# watch_1_2.net
KiCad netlist of a schematic drawn in EAGLE
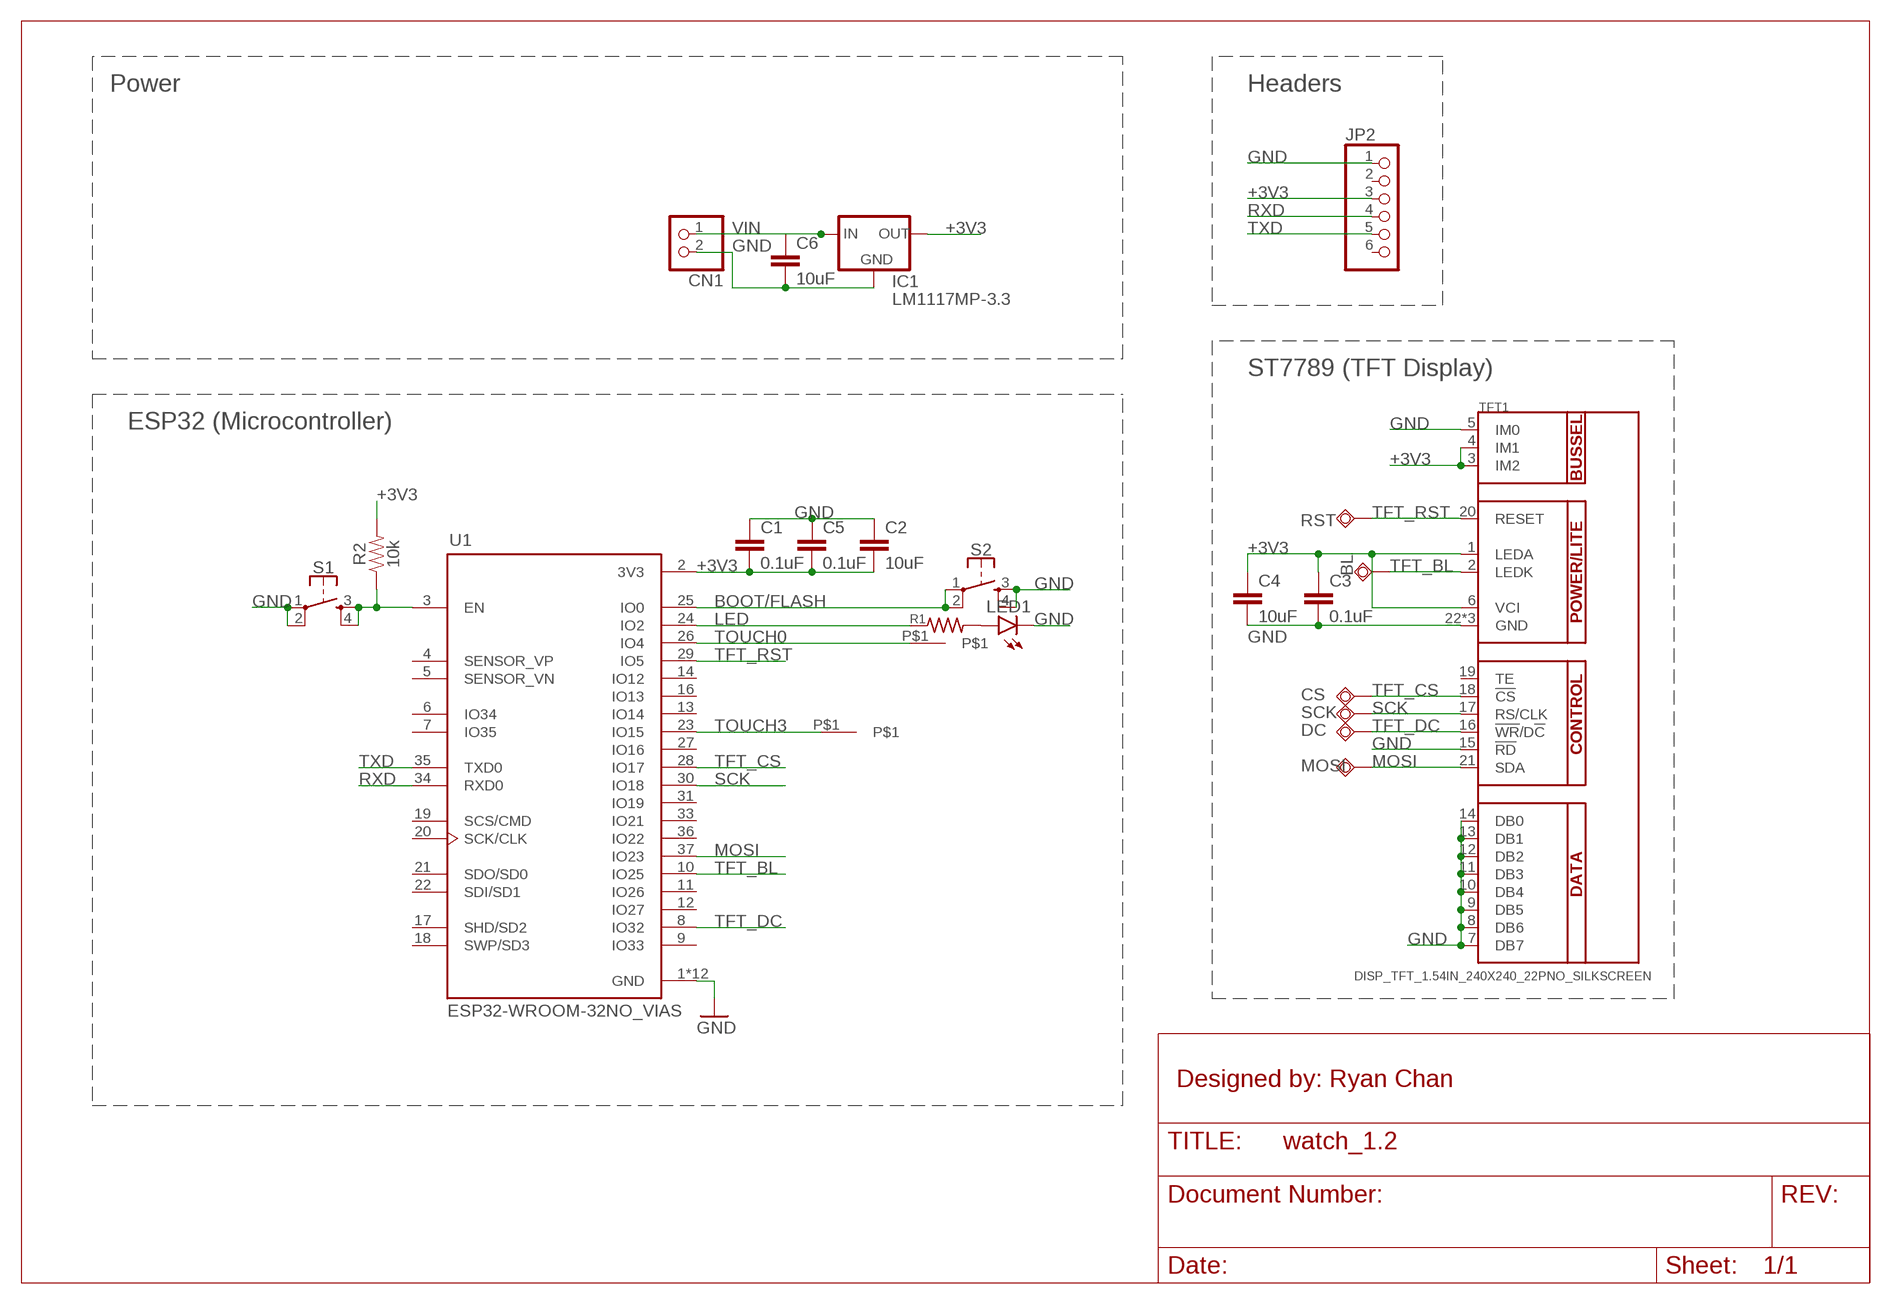
[diagram p0: schematic, sheet 1]

(export (version "E")
  (design (tool "Eeschema 10.0.6"))
  (components
    (comp (ref "BL")
      (value "TPSQTP20R")
      (footprint "eagle-import:TP20R")
      (libsource (lib "eagle-import") (part "TPSQTP20R"))
    )
    (comp (ref "C1")
      (value "0.1uF")
      (footprint "eagle-import:C0603")
      (libsource (lib "eagle-import") (part "C-EUC0603"))
    )
    (comp (ref "C2")
      (value "10uF")
      (footprint "eagle-import:C0603")
      (libsource (lib "eagle-import") (part "C-EUC0603"))
    )
    (comp (ref "C3")
      (value "0.1uF")
      (footprint "eagle-import:C0603")
      (libsource (lib "eagle-import") (part "C-EUC0603"))
    )
    (comp (ref "C4")
      (value "10uF")
      (footprint "eagle-import:C0603")
      (libsource (lib "eagle-import") (part "C-EUC0603"))
    )
    (comp (ref "C5")
      (value "0.1uF")
      (footprint "eagle-import:C0603")
      (libsource (lib "eagle-import") (part "C-EUC0603"))
    )
    (comp (ref "C6")
      (value "10uF")
      (footprint "eagle-import:C0603")
      (libsource (lib "eagle-import") (part "C-EUC0603"))
    )
    (comp (ref "CN1")
      (value "JST_2PIN-SMT-RA")
      (footprint "eagle-import:JST-PH-2-SMT-RA")
      (libsource (lib "eagle-import") (part "JST_2PIN-SMT-RA"))
    )
    (comp (ref "CS")
      (value "TPSQTP20R")
      (footprint "eagle-import:TP20R")
      (libsource (lib "eagle-import") (part "TPSQTP20R"))
    )
    (comp (ref "DC")
      (value "TPSQTP20R")
      (footprint "eagle-import:TP20R")
      (libsource (lib "eagle-import") (part "TPSQTP20R"))
    )
    (comp (ref "IC1")
      (value "LM1117MP-3.3")
      (footprint "eagle-import:SOT223")
      (fields (field (name "MF") "Texas Instruments"))
      (libsource (lib "eagle-import") (part "LM1117?-MP3.3"))
    )
    (comp (ref "JP2")
      (value "PINHD-1X6CLEAN")
      (footprint "eagle-import:1X06-CLEAN")
      (libsource (lib "eagle-import") (part "PINHD-1X6CLEAN"))
    )
    (comp (ref "LED1")
      (value "LEDCHIPLED_0603")
      (footprint "eagle-import:CHIPLED_0603")
      (libsource (lib "eagle-import") (part "LEDCHIPLED_0603"))
    )
    (comp (ref "MOSI")
      (value "TPSQTP20R")
      (footprint "eagle-import:TP20R")
      (libsource (lib "eagle-import") (part "TPSQTP20R"))
    )
    (comp (ref "R1")
      (value "R-US_R0603")
      (footprint "eagle-import:R0603")
      (libsource (lib "eagle-import") (part "R-US_R0603"))
    )
    (comp (ref "R2")
      (value "10k")
      (footprint "eagle-import:0603")
      (libsource (lib "eagle-import") (part "10KOHM-0603-1/10W-1%"))
    )
    (comp (ref "RST")
      (value "TPSQTP20R")
      (footprint "eagle-import:TP20R")
      (libsource (lib "eagle-import") (part "TPSQTP20R"))
    )
    (comp (ref "S1")
      (value "RESET")
      (footprint "eagle-import:TACTILE_SWITCH_SMD_4.6X2.8MM")
      (libsource (lib "eagle-import") (part "MOMENTARY-SWITCH-SPST-2-SMD-4.6X2.8MM"))
    )
    (comp (ref "S2")
      (value "RESET")
      (footprint "eagle-import:TACTILE_SWITCH_SMD_4.6X2.8MM")
      (libsource (lib "eagle-import") (part "MOMENTARY-SWITCH-SPST-2-SMD-4.6X2.8MM"))
    )
    (comp (ref "SCK")
      (value "TPSQTP20R")
      (footprint "eagle-import:TP20R")
      (libsource (lib "eagle-import") (part "TPSQTP20R"))
    )
    (comp (ref "TFT1")
      (value "DISP_TFT_1.54IN_240X240_22PNO_SILKSCREEN")
      (footprint "eagle-import:TFT_1.54IN_240X240_22PIN_NO_SILKSCREEN")
      (libsource (lib "eagle-import") (part "DISP_TFT_1.54IN_240X240_22PNO_SILKSCREEN"))
    )
    (comp (ref "U$1")
      (value "CAPACITIVE_PAD_1")
      (footprint "eagle-import:CAPACITIVE_PAD_1")
      (libsource (lib "eagle-import") (part "CAPACITIVE_PAD_1"))
    )
    (comp (ref "U$2")
      (value "CAPACITIVE_PAD_1")
      (footprint "eagle-import:CAPACITIVE_PAD_1")
      (libsource (lib "eagle-import") (part "CAPACITIVE_PAD_1"))
    )
    (comp (ref "U1")
      (value "ESP32-WROOM-32NO_VIAS")
      (footprint "eagle-import:MODULE_ESP32-WROOM-32_NO_VIAS")
      (libsource (lib "eagle-import") (part "ESP32-WROOM-32NO_VIAS"))
    )
  )
  (nets
    (net (code "1") (name "/+3V3") (class "Default")
      (node (ref "C1") (pin "2") (pinfunction "2_2") (pintype "passive"))
      (node (ref "C2") (pin "2") (pinfunction "2_2") (pintype "passive"))
      (node (ref "C3") (pin "1") (pinfunction "1_1") (pintype "passive"))
      (node (ref "C4") (pin "1") (pinfunction "1_1") (pintype "passive"))
      (node (ref "C5") (pin "2") (pinfunction "2_2") (pintype "passive"))
      (node (ref "IC1") (pin "2") (pinfunction "OUT_2") (pintype "passive"))
      (node (ref "IC1") (pin "4") (pinfunction "OUT_4") (pintype "passive"))
      (node (ref "JP2") (pin "3") (pinfunction "3_3") (pintype "passive"))
      (node (ref "R2") (pin "2") (pinfunction "2_2") (pintype "passive"))
      (node (ref "TFT1") (pin "1") (pinfunction "LEDA_1") (pintype "input"))
      (node (ref "TFT1") (pin "3") (pinfunction "IM2_3") (pintype "input"))
      (node (ref "TFT1") (pin "4") (pinfunction "IM1_4") (pintype "input"))
      (node (ref "TFT1") (pin "6") (pinfunction "VCI_6") (pintype "power_in"))
      (node (ref "U1") (pin "2") (pinfunction "3V3_2") (pintype "power_in"))
    )
    (net (code "2") (name "/BOOT{slash}FLASH") (class "Default")
      (node (ref "S2") (pin "1") (pinfunction "1_1") (pintype "passive"))
      (node (ref "S2") (pin "2") (pinfunction "2_2") (pintype "passive"))
      (node (ref "U1") (pin "25") (pinfunction "IO0_25") (pintype "bidirectional"))
    )
    (net (code "3") (name "/LED") (class "Default")
      (node (ref "R1") (pin "1") (pinfunction "1_1") (pintype "passive"))
      (node (ref "U1") (pin "24") (pinfunction "IO2_24") (pintype "bidirectional"))
    )
    (net (code "4") (name "/MOSI") (class "Default")
      (node (ref "MOSI") (pin "TP") (pinfunction "TP_TP") (pintype "input"))
      (node (ref "TFT1") (pin "21") (pinfunction "SDA_21") (pintype "bidirectional"))
      (node (ref "U1") (pin "37") (pinfunction "IO23_37") (pintype "bidirectional"))
    )
    (net (code "5") (name "/RXD") (class "Default")
      (node (ref "JP2") (pin "4") (pinfunction "4_4") (pintype "passive"))
      (node (ref "U1") (pin "34") (pinfunction "RXD0_34") (pintype "bidirectional"))
    )
    (net (code "6") (name "/SCK") (class "Default")
      (node (ref "SCK") (pin "TP") (pinfunction "TP_TP") (pintype "input"))
      (node (ref "TFT1") (pin "17") (pinfunction "RS/CLK_17") (pintype "input"))
      (node (ref "U1") (pin "30") (pinfunction "IO18_30") (pintype "bidirectional"))
    )
    (net (code "7") (name "/TFT_BL") (class "Default")
      (node (ref "BL") (pin "TP") (pinfunction "TP_TP") (pintype "input"))
      (node (ref "TFT1") (pin "2") (pinfunction "LEDK_2") (pintype "input"))
      (node (ref "U1") (pin "10") (pinfunction "IO25_10") (pintype "bidirectional"))
    )
    (net (code "8") (name "/TFT_CS") (class "Default")
      (node (ref "CS") (pin "TP") (pinfunction "TP_TP") (pintype "input"))
      (node (ref "TFT1") (pin "18") (pinfunction "~{CS}_18") (pintype "input"))
      (node (ref "U1") (pin "28") (pinfunction "IO17_28") (pintype "bidirectional"))
    )
    (net (code "9") (name "/TFT_DC") (class "Default")
      (node (ref "DC") (pin "TP") (pinfunction "TP_TP") (pintype "input"))
      (node (ref "TFT1") (pin "16") (pinfunction "~{WR}/D~{C}_16") (pintype "input"))
      (node (ref "U1") (pin "8") (pinfunction "IO32_8") (pintype "bidirectional"))
    )
    (net (code "10") (name "/TFT_RST") (class "Default")
      (node (ref "RST") (pin "TP") (pinfunction "TP_TP") (pintype "input"))
      (node (ref "TFT1") (pin "20") (pinfunction "RESET_20") (pintype "input"))
      (node (ref "U1") (pin "29") (pinfunction "IO5_29") (pintype "bidirectional"))
    )
    (net (code "11") (name "/TOUCH0") (class "Default")
      (node (ref "U$2") (pin "P$1") (pinfunction "P$1_P$1") (pintype "bidirectional"))
      (node (ref "U1") (pin "26") (pinfunction "IO4_26") (pintype "bidirectional"))
    )
    (net (code "12") (name "/TOUCH3") (class "Default")
      (node (ref "U$1") (pin "P$1") (pinfunction "P$1_P$1") (pintype "bidirectional"))
      (node (ref "U1") (pin "23") (pinfunction "IO15_23") (pintype "bidirectional"))
    )
    (net (code "13") (name "/TXD") (class "Default")
      (node (ref "JP2") (pin "5") (pinfunction "5_5") (pintype "passive"))
      (node (ref "U1") (pin "35") (pinfunction "TXD0_35") (pintype "bidirectional"))
    )
    (net (code "14") (name "/VIN") (class "Default")
      (node (ref "C6") (pin "1") (pinfunction "1_1") (pintype "passive"))
      (node (ref "CN1") (pin "1") (pinfunction "2_1") (pintype "passive"))
      (node (ref "IC1") (pin "3") (pinfunction "IN_3") (pintype "input"))
    )
    (net (code "15") (name "GND") (class "Default")
      (node (ref "C1") (pin "1") (pinfunction "1_1") (pintype "passive"))
      (node (ref "C2") (pin "1") (pinfunction "1_1") (pintype "passive"))
      (node (ref "C3") (pin "2") (pinfunction "2_2") (pintype "passive"))
      (node (ref "C4") (pin "2") (pinfunction "2_2") (pintype "passive"))
      (node (ref "C5") (pin "1") (pinfunction "1_1") (pintype "passive"))
      (node (ref "C6") (pin "2") (pinfunction "2_2") (pintype "passive"))
      (node (ref "CN1") (pin "2") (pinfunction "1_2") (pintype "passive"))
      (node (ref "IC1") (pin "1") (pinfunction "GND_1") (pintype "input"))
      (node (ref "JP2") (pin "1") (pinfunction "1_1") (pintype "passive"))
      (node (ref "LED1") (pin "C") (pinfunction "C_C") (pintype "passive"))
      (node (ref "S1") (pin "1") (pinfunction "1_1") (pintype "passive"))
      (node (ref "S1") (pin "2") (pinfunction "2_2") (pintype "passive"))
      (node (ref "S2") (pin "3") (pinfunction "3_3") (pintype "passive"))
      (node (ref "S2") (pin "4") (pinfunction "4_4") (pintype "passive"))
      (node (ref "TFT1") (pin "10") (pinfunction "DB4_10") (pintype "bidirectional"))
      (node (ref "TFT1") (pin "11") (pinfunction "DB3_11") (pintype "bidirectional"))
      (node (ref "TFT1") (pin "12") (pinfunction "DB2_12") (pintype "bidirectional"))
      (node (ref "TFT1") (pin "13") (pinfunction "DB1_13") (pintype "bidirectional"))
      (node (ref "TFT1") (pin "14") (pinfunction "DB0_14") (pintype "bidirectional"))
      (node (ref "TFT1") (pin "15") (pinfunction "~{RD}_15") (pintype "input"))
      (node (ref "TFT1") (pin "22") (pinfunction "GND_22") (pintype "power_in"))
      (node (ref "TFT1") (pin "5") (pinfunction "IM0_5") (pintype "input"))
      (node (ref "TFT1") (pin "7") (pinfunction "DB7_7") (pintype "bidirectional"))
      (node (ref "TFT1") (pin "8") (pinfunction "DB6_8") (pintype "bidirectional"))
      (node (ref "TFT1") (pin "9") (pinfunction "DB5_9") (pintype "bidirectional"))
      (node (ref "TFT1") (pin "SUPPORT1") (pinfunction "GND_SUPPORT1") (pintype "power_in"))
      (node (ref "TFT1") (pin "SUPPORT2") (pinfunction "GND_SUPPORT2") (pintype "power_in"))
      (node (ref "U1") (pin "1") (pinfunction "GND_1") (pintype "power_in"))
      (node (ref "U1") (pin "15") (pinfunction "GND_15") (pintype "power_in"))
      (node (ref "U1") (pin "38") (pinfunction "GND_38") (pintype "power_in"))
      (node (ref "U1") (pin "39_1") (pinfunction "GND_39_1") (pintype "power_in"))
      (node (ref "U1") (pin "39_2") (pinfunction "GND_39_2") (pintype "power_in"))
      (node (ref "U1") (pin "39_3") (pinfunction "GND_39_3") (pintype "power_in"))
      (node (ref "U1") (pin "39_4") (pinfunction "GND_39_4") (pintype "power_in"))
      (node (ref "U1") (pin "39_5") (pinfunction "GND_39_5") (pintype "power_in"))
      (node (ref "U1") (pin "39_6") (pinfunction "GND_39_6") (pintype "power_in"))
      (node (ref "U1") (pin "39_7") (pinfunction "GND_39_7") (pintype "power_in"))
      (node (ref "U1") (pin "39_8") (pinfunction "GND_39_8") (pintype "power_in"))
      (node (ref "U1") (pin "39_9") (pinfunction "GND_39_9") (pintype "power_in"))
    )
    (net (code "16") (name "Net-(LED1-PadA)") (class "Default")
      (node (ref "LED1") (pin "A") (pinfunction "A_A") (pintype "passive"))
      (node (ref "R1") (pin "2") (pinfunction "2_2") (pintype "passive"))
    )
    (net (code "17") (name "Net-(U1-EN)") (class "Default")
      (node (ref "R2") (pin "1") (pinfunction "1_1") (pintype "passive"))
      (node (ref "S1") (pin "3") (pinfunction "3_3") (pintype "passive"))
      (node (ref "S1") (pin "4") (pinfunction "4_4") (pintype "passive"))
      (node (ref "U1") (pin "3") (pinfunction "EN_3") (pintype "input"))
    )
    (net (code "18") (name "unconnected-(JP2-Pad2)") (class "Default")
      (node (ref "JP2") (pin "2") (pinfunction "2_2") (pintype "passive"))
    )
    (net (code "19") (name "unconnected-(JP2-Pad6)") (class "Default")
      (node (ref "JP2") (pin "6") (pinfunction "6_6") (pintype "passive"))
    )
    (net (code "20") (name "unconnected-(TFT1-TE-Pad19)") (class "Default")
      (node (ref "TFT1") (pin "19") (pinfunction "TE_19") (pintype "output"))
    )
    (net (code "21") (name "unconnected-(U1-IO12-Pad14)") (class "Default")
      (node (ref "U1") (pin "14") (pinfunction "IO12_14") (pintype "bidirectional"))
    )
    (net (code "22") (name "unconnected-(U1-IO13-Pad16)") (class "Default")
      (node (ref "U1") (pin "16") (pinfunction "IO13_16") (pintype "bidirectional"))
    )
    (net (code "23") (name "unconnected-(U1-IO14-Pad13)") (class "Default")
      (node (ref "U1") (pin "13") (pinfunction "IO14_13") (pintype "bidirectional"))
    )
    (net (code "24") (name "unconnected-(U1-IO16-Pad27)") (class "Default")
      (node (ref "U1") (pin "27") (pinfunction "IO16_27") (pintype "bidirectional"))
    )
    (net (code "25") (name "unconnected-(U1-IO19-Pad31)") (class "Default")
      (node (ref "U1") (pin "31") (pinfunction "IO19_31") (pintype "bidirectional"))
    )
    (net (code "26") (name "unconnected-(U1-IO21-Pad33)") (class "Default")
      (node (ref "U1") (pin "33") (pinfunction "IO21_33") (pintype "bidirectional"))
    )
    (net (code "27") (name "unconnected-(U1-IO22-Pad36)") (class "Default")
      (node (ref "U1") (pin "36") (pinfunction "IO22_36") (pintype "bidirectional"))
    )
    (net (code "28") (name "unconnected-(U1-IO26-Pad11)") (class "Default")
      (node (ref "U1") (pin "11") (pinfunction "IO26_11") (pintype "bidirectional"))
    )
    (net (code "29") (name "unconnected-(U1-IO27-Pad12)") (class "Default")
      (node (ref "U1") (pin "12") (pinfunction "IO27_12") (pintype "bidirectional"))
    )
    (net (code "30") (name "unconnected-(U1-IO33-Pad9)") (class "Default")
      (node (ref "U1") (pin "9") (pinfunction "IO33_9") (pintype "bidirectional"))
    )
    (net (code "31") (name "unconnected-(U1-IO34-Pad6)") (class "Default")
      (node (ref "U1") (pin "6") (pinfunction "IO34_6") (pintype "input"))
    )
    (net (code "32") (name "unconnected-(U1-IO35-Pad7)") (class "Default")
      (node (ref "U1") (pin "7") (pinfunction "IO35_7") (pintype "input"))
    )
    (net (code "33") (name "unconnected-(U1-SCK{slash}CLK-Pad20)") (class "Default")
      (node (ref "U1") (pin "20") (pinfunction "SCK/CLK_20") (pintype "bidirectional"))
    )
    (net (code "34") (name "unconnected-(U1-SCS{slash}CMD-Pad19)") (class "Default")
      (node (ref "U1") (pin "19") (pinfunction "SCS/CMD_19") (pintype "bidirectional"))
    )
    (net (code "35") (name "unconnected-(U1-SDI{slash}SD1-Pad22)") (class "Default")
      (node (ref "U1") (pin "22") (pinfunction "SDI/SD1_22") (pintype "bidirectional"))
    )
    (net (code "36") (name "unconnected-(U1-SDO{slash}SD0-Pad21)") (class "Default")
      (node (ref "U1") (pin "21") (pinfunction "SDO/SD0_21") (pintype "bidirectional"))
    )
    (net (code "37") (name "unconnected-(U1-SENSOR_VN-Pad5)") (class "Default")
      (node (ref "U1") (pin "5") (pinfunction "SENSOR_VN_5") (pintype "input"))
    )
    (net (code "38") (name "unconnected-(U1-SENSOR_VP-Pad4)") (class "Default")
      (node (ref "U1") (pin "4") (pinfunction "SENSOR_VP_4") (pintype "input"))
    )
    (net (code "39") (name "unconnected-(U1-SHD{slash}SD2-Pad17)") (class "Default")
      (node (ref "U1") (pin "17") (pinfunction "SHD/SD2_17") (pintype "bidirectional"))
    )
    (net (code "40") (name "unconnected-(U1-SWP{slash}SD3-Pad18)") (class "Default")
      (node (ref "U1") (pin "18") (pinfunction "SWP/SD3_18") (pintype "bidirectional"))
    )
  )
)
